# ElekShemaRelais.net
KiCad netlist of a schematic drawn in Altium Designer
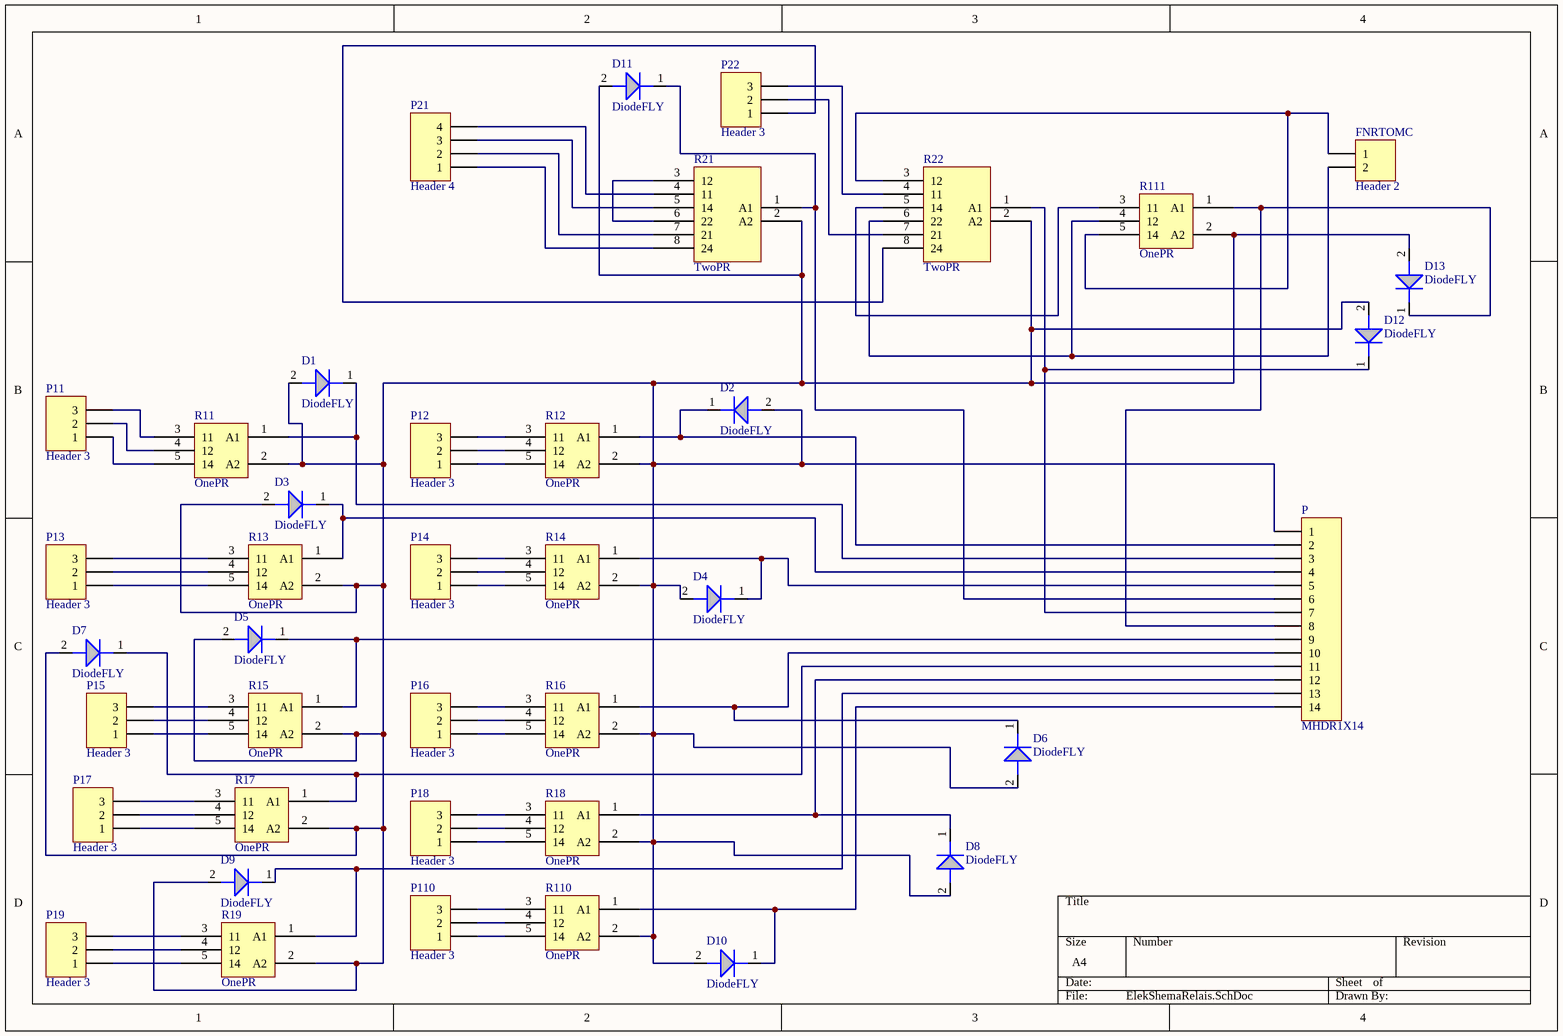
[diagram p0: ElekShemaRelais.SchDoc]

(export (version "E")
  (design (tool "Eeschema 10.0.6"))
  (components
    (comp (ref "D1") (value "DiodeFLY") (footprint "DiodeFLY") (libsource (lib "Schlib1") (part "DiodeFLY")))
    (comp (ref "D2") (value "DiodeFLY") (footprint "DiodeFLY") (libsource (lib "Schlib1") (part "DiodeFLY")))
    (comp (ref "D3") (value "DiodeFLY") (footprint "DiodeFLY") (libsource (lib "Schlib1") (part "DiodeFLY")))
    (comp (ref "D4") (value "DiodeFLY") (footprint "DiodeFLY") (libsource (lib "Schlib1") (part "DiodeFLY")))
    (comp (ref "D5") (value "DiodeFLY") (footprint "DiodeFLY") (libsource (lib "Schlib1") (part "DiodeFLY")))
    (comp (ref "D6") (value "DiodeFLY") (footprint "DiodeFLY") (libsource (lib "Schlib1") (part "DiodeFLY")))
    (comp (ref "D7") (value "DiodeFLY") (footprint "DiodeFLY") (libsource (lib "Schlib1") (part "DiodeFLY")))
    (comp (ref "D8") (value "DiodeFLY") (footprint "DiodeFLY") (libsource (lib "Schlib1") (part "DiodeFLY")))
    (comp (ref "D9") (value "DiodeFLY") (footprint "DiodeFLY") (libsource (lib "Schlib1") (part "DiodeFLY")))
    (comp (ref "D10") (value "DiodeFLY") (footprint "DiodeFLY") (libsource (lib "Schlib1") (part "DiodeFLY")))
    (comp (ref "D11") (value "DiodeFLY") (footprint "DiodeFLY") (libsource (lib "Schlib1") (part "DiodeFLY")))
    (comp (ref "D12") (value "DiodeFLY") (footprint "DiodeFLY") (libsource (lib "Schlib1") (part "DiodeFLY")))
    (comp (ref "D13") (value "DiodeFLY") (footprint "DiodeFLY") (libsource (lib "Schlib1") (part "DiodeFLY")))
    (comp (ref "FNRTOMC")
      (value "Header 2")
      (footprint "HDR2")
      (description "Header, 2-Pin")
      (fields (field (name "PUBLISHER") "Altium Limited"))
      (libsource (lib "Miscellaneous Connectors") (part "Header 2"))
    )
    (comp (ref "P")
      (value "MHDR1X14")
      (footprint "HDR14")
      (description "Header, 14-Pin")
      (fields (field (name "PUBLISHER") "Altium Limited"))
      (libsource (lib "Miscellaneous Connectors") (part "MHDR1X14"))
    )
    (comp (ref "P11")
      (value "Header 3")
      (footprint "HDR3")
      (description "Header, 3-Pin")
      (fields (field (name "PUBLISHER") "Altium Limited"))
      (libsource (lib "Miscellaneous Connectors") (part "Header 3"))
    )
    (comp (ref "P12")
      (value "Header 3")
      (footprint "HDR3")
      (description "Header, 3-Pin")
      (fields (field (name "PUBLISHER") "Altium Limited"))
      (libsource (lib "Miscellaneous Connectors") (part "Header 3"))
    )
    (comp (ref "P13")
      (value "Header 3")
      (footprint "HDR3")
      (description "Header, 3-Pin")
      (fields (field (name "PUBLISHER") "Altium Limited"))
      (libsource (lib "Miscellaneous Connectors") (part "Header 3"))
    )
    (comp (ref "P14")
      (value "Header 3")
      (footprint "HDR3")
      (description "Header, 3-Pin")
      (fields (field (name "PUBLISHER") "Altium Limited"))
      (libsource (lib "Miscellaneous Connectors") (part "Header 3"))
    )
    (comp (ref "P15")
      (value "Header 3")
      (footprint "HDR3")
      (description "Header, 3-Pin")
      (fields (field (name "PUBLISHER") "Altium Limited"))
      (libsource (lib "Miscellaneous Connectors") (part "Header 3"))
    )
    (comp (ref "P16")
      (value "Header 3")
      (footprint "HDR3")
      (description "Header, 3-Pin")
      (fields (field (name "PUBLISHER") "Altium Limited"))
      (libsource (lib "Miscellaneous Connectors") (part "Header 3"))
    )
    (comp (ref "P17")
      (value "Header 3")
      (footprint "HDR3")
      (description "Header, 3-Pin")
      (fields (field (name "PUBLISHER") "Altium Limited"))
      (libsource (lib "Miscellaneous Connectors") (part "Header 3"))
    )
    (comp (ref "P18")
      (value "Header 3")
      (footprint "HDR3")
      (description "Header, 3-Pin")
      (fields (field (name "PUBLISHER") "Altium Limited"))
      (libsource (lib "Miscellaneous Connectors") (part "Header 3"))
    )
    (comp (ref "P19")
      (value "Header 3")
      (footprint "HDR3")
      (description "Header, 3-Pin")
      (fields (field (name "PUBLISHER") "Altium Limited"))
      (libsource (lib "Miscellaneous Connectors") (part "Header 3"))
    )
    (comp (ref "P21")
      (value "Header 4")
      (footprint "HDR4")
      (description "Header, 4-Pin")
      (fields (field (name "PUBLISHER") "Altium Limited"))
      (libsource (lib "Miscellaneous Connectors") (part "Header 4"))
    )
    (comp (ref "P22")
      (value "Header 3")
      (footprint "HDR3")
      (description "Header, 3-Pin")
      (fields (field (name "PUBLISHER") "Altium Limited"))
      (libsource (lib "Miscellaneous Connectors") (part "Header 3"))
    )
    (comp (ref "P110")
      (value "Header 3")
      (footprint "HDR3")
      (description "Header, 3-Pin")
      (fields (field (name "PUBLISHER") "Altium Limited"))
      (libsource (lib "Miscellaneous Connectors") (part "Header 3"))
    )
    (comp (ref "R11") (value "OnePR") (footprint "EENPOOL") (libsource (lib "Schlib1") (part "R1")))
    (comp (ref "R12") (value "OnePR") (footprint "EENPOOL") (libsource (lib "Schlib1") (part "R1")))
    (comp (ref "R13") (value "OnePR") (footprint "EENPOOL") (libsource (lib "Schlib1") (part "R1")))
    (comp (ref "R14") (value "OnePR") (footprint "EENPOOL") (libsource (lib "Schlib1") (part "R1")))
    (comp (ref "R15") (value "OnePR") (footprint "EENPOOL") (libsource (lib "Schlib1") (part "R1")))
    (comp (ref "R16") (value "OnePR") (footprint "EENPOOL") (libsource (lib "Schlib1") (part "R1")))
    (comp (ref "R17") (value "OnePR") (footprint "EENPOOL") (libsource (lib "Schlib1") (part "R1")))
    (comp (ref "R18") (value "OnePR") (footprint "EENPOOL") (libsource (lib "Schlib1") (part "R1")))
    (comp (ref "R19") (value "OnePR") (footprint "EENPOOL") (libsource (lib "Schlib1") (part "R1")))
    (comp (ref "R21") (value "TwoPR") (footprint "TWEEPOOL") (libsource (lib "Schlib1") (part "R2")))
    (comp (ref "R22") (value "TwoPR") (footprint "TWEEPOOL") (libsource (lib "Schlib1") (part "R2")))
    (comp (ref "R110") (value "OnePR") (footprint "EENPOOL") (libsource (lib "Schlib1") (part "R1")))
    (comp (ref "R111") (value "OnePR") (footprint "EENPOOL") (libsource (lib "Schlib1") (part "R1")))
  )
  (nets
    (net (code "1") (name "Net-(R11-11)") (class "Default")
      (node (ref "P11") (pin "3") (pinfunction "3_3") (pintype "passive"))
      (node (ref "R11") (pin "3") (pinfunction "11_3") (pintype "passive"))
    )
    (net (code "2") (name "Net-(R11-12)") (class "Default")
      (node (ref "P11") (pin "2") (pinfunction "2_2") (pintype "passive"))
      (node (ref "R11") (pin "4") (pinfunction "12_4") (pintype "passive"))
    )
    (net (code "3") (name "Net-(R11-14)") (class "Default")
      (node (ref "P11") (pin "1") (pinfunction "1_1") (pintype "passive"))
      (node (ref "R11") (pin "5") (pinfunction "14_5") (pintype "passive"))
    )
    (net (code "4") (name "Net-(R11-A1)") (class "Default")
      (node (ref "D1") (pin "1") (pintype "passive"))
      (node (ref "P") (pin "3") (pinfunction "3_3") (pintype "passive"))
      (node (ref "R11") (pin "1") (pinfunction "A1_1") (pintype "passive"))
    )
    (net (code "5") (name "Net-(R11-A2)") (class "Default")
      (node (ref "D1") (pin "2") (pintype "passive"))
      (node (ref "D10") (pin "2") (pintype "passive"))
      (node (ref "D11") (pin "2") (pintype "passive"))
      (node (ref "D12") (pin "2") (pintype "passive"))
      (node (ref "D13") (pin "2") (pintype "passive"))
      (node (ref "D2") (pin "2") (pintype "passive"))
      (node (ref "D3") (pin "2") (pintype "passive"))
      (node (ref "D4") (pin "2") (pintype "passive"))
      (node (ref "D5") (pin "2") (pintype "passive"))
      (node (ref "D6") (pin "2") (pintype "passive"))
      (node (ref "D7") (pin "2") (pintype "passive"))
      (node (ref "D8") (pin "2") (pintype "passive"))
      (node (ref "D9") (pin "2") (pintype "passive"))
      (node (ref "P") (pin "1") (pinfunction "1_1") (pintype "passive"))
      (node (ref "R11") (pin "2") (pinfunction "A2_2") (pintype "passive"))
      (node (ref "R110") (pin "2") (pinfunction "A2_2") (pintype "passive"))
      (node (ref "R111") (pin "2") (pinfunction "A2_2") (pintype "passive"))
      (node (ref "R12") (pin "2") (pinfunction "A2_2") (pintype "passive"))
      (node (ref "R13") (pin "2") (pinfunction "A2_2") (pintype "passive"))
      (node (ref "R14") (pin "2") (pinfunction "A2_2") (pintype "passive"))
      (node (ref "R15") (pin "2") (pinfunction "A2_2") (pintype "passive"))
      (node (ref "R16") (pin "2") (pinfunction "A2_2") (pintype "passive"))
      (node (ref "R17") (pin "2") (pinfunction "A2_2") (pintype "passive"))
      (node (ref "R18") (pin "2") (pinfunction "A2_2") (pintype "passive"))
      (node (ref "R19") (pin "2") (pinfunction "A2_2") (pintype "passive"))
      (node (ref "R21") (pin "2") (pinfunction "A2_2") (pintype "passive"))
      (node (ref "R22") (pin "2") (pinfunction "A2_2") (pintype "passive"))
    )
    (net (code "6") (name "Net-(R12-11)") (class "Default")
      (node (ref "P12") (pin "3") (pinfunction "3_3") (pintype "passive"))
      (node (ref "R12") (pin "3") (pinfunction "11_3") (pintype "passive"))
    )
    (net (code "7") (name "Net-(R12-12)") (class "Default")
      (node (ref "P12") (pin "2") (pinfunction "2_2") (pintype "passive"))
      (node (ref "R12") (pin "4") (pinfunction "12_4") (pintype "passive"))
    )
    (net (code "8") (name "Net-(R12-14)") (class "Default")
      (node (ref "P12") (pin "1") (pinfunction "1_1") (pintype "passive"))
      (node (ref "R12") (pin "5") (pinfunction "14_5") (pintype "passive"))
    )
    (net (code "9") (name "Net-(R12-A1)") (class "Default")
      (node (ref "D2") (pin "1") (pintype "passive"))
      (node (ref "P") (pin "2") (pinfunction "2_2") (pintype "passive"))
      (node (ref "R12") (pin "1") (pinfunction "A1_1") (pintype "passive"))
    )
    (net (code "10") (name "Net-(R13-11)") (class "Default")
      (node (ref "P13") (pin "3") (pinfunction "3_3") (pintype "passive"))
      (node (ref "R13") (pin "3") (pinfunction "11_3") (pintype "passive"))
    )
    (net (code "11") (name "Net-(R13-12)") (class "Default")
      (node (ref "P13") (pin "2") (pinfunction "2_2") (pintype "passive"))
      (node (ref "R13") (pin "4") (pinfunction "12_4") (pintype "passive"))
    )
    (net (code "12") (name "Net-(R13-14)") (class "Default")
      (node (ref "P13") (pin "1") (pinfunction "1_1") (pintype "passive"))
      (node (ref "R13") (pin "5") (pinfunction "14_5") (pintype "passive"))
    )
    (net (code "13") (name "Net-(R13-A1)") (class "Default")
      (node (ref "D3") (pin "1") (pintype "passive"))
      (node (ref "P") (pin "4") (pinfunction "4_4") (pintype "passive"))
      (node (ref "R13") (pin "1") (pinfunction "A1_1") (pintype "passive"))
    )
    (net (code "14") (name "Net-(R14-11)") (class "Default")
      (node (ref "P14") (pin "3") (pinfunction "3_3") (pintype "passive"))
      (node (ref "R14") (pin "3") (pinfunction "11_3") (pintype "passive"))
    )
    (net (code "15") (name "Net-(R14-12)") (class "Default")
      (node (ref "P14") (pin "2") (pinfunction "2_2") (pintype "passive"))
      (node (ref "R14") (pin "4") (pinfunction "12_4") (pintype "passive"))
    )
    (net (code "16") (name "Net-(R14-14)") (class "Default")
      (node (ref "P14") (pin "1") (pinfunction "1_1") (pintype "passive"))
      (node (ref "R14") (pin "5") (pinfunction "14_5") (pintype "passive"))
    )
    (net (code "17") (name "Net-(R14-A1)") (class "Default")
      (node (ref "D4") (pin "1") (pintype "passive"))
      (node (ref "P") (pin "5") (pinfunction "5_5") (pintype "passive"))
      (node (ref "R14") (pin "1") (pinfunction "A1_1") (pintype "passive"))
    )
    (net (code "18") (name "Net-(R15-11)") (class "Default")
      (node (ref "P15") (pin "3") (pinfunction "3_3") (pintype "passive"))
      (node (ref "R15") (pin "3") (pinfunction "11_3") (pintype "passive"))
    )
    (net (code "19") (name "Net-(R15-12)") (class "Default")
      (node (ref "P15") (pin "2") (pinfunction "2_2") (pintype "passive"))
      (node (ref "R15") (pin "4") (pinfunction "12_4") (pintype "passive"))
    )
    (net (code "20") (name "Net-(R15-14)") (class "Default")
      (node (ref "P15") (pin "1") (pinfunction "1_1") (pintype "passive"))
      (node (ref "R15") (pin "5") (pinfunction "14_5") (pintype "passive"))
    )
    (net (code "21") (name "Net-(R15-A1)") (class "Default")
      (node (ref "D5") (pin "1") (pintype "passive"))
      (node (ref "P") (pin "9") (pinfunction "9_9") (pintype "passive"))
      (node (ref "R15") (pin "1") (pinfunction "A1_1") (pintype "passive"))
    )
    (net (code "22") (name "Net-(R16-11)") (class "Default")
      (node (ref "P16") (pin "3") (pinfunction "3_3") (pintype "passive"))
      (node (ref "R16") (pin "3") (pinfunction "11_3") (pintype "passive"))
    )
    (net (code "23") (name "Net-(R16-12)") (class "Default")
      (node (ref "P16") (pin "2") (pinfunction "2_2") (pintype "passive"))
      (node (ref "R16") (pin "4") (pinfunction "12_4") (pintype "passive"))
    )
    (net (code "24") (name "Net-(R16-14)") (class "Default")
      (node (ref "P16") (pin "1") (pinfunction "1_1") (pintype "passive"))
      (node (ref "R16") (pin "5") (pinfunction "14_5") (pintype "passive"))
    )
    (net (code "25") (name "Net-(R16-A1)") (class "Default")
      (node (ref "D6") (pin "1") (pintype "passive"))
      (node (ref "P") (pin "10") (pinfunction "10_10") (pintype "passive"))
      (node (ref "R16") (pin "1") (pinfunction "A1_1") (pintype "passive"))
    )
    (net (code "26") (name "Net-(R17-11)") (class "Default")
      (node (ref "P17") (pin "3") (pinfunction "3_3") (pintype "passive"))
      (node (ref "R17") (pin "3") (pinfunction "11_3") (pintype "passive"))
    )
    (net (code "27") (name "Net-(R17-12)") (class "Default")
      (node (ref "P17") (pin "2") (pinfunction "2_2") (pintype "passive"))
      (node (ref "R17") (pin "4") (pinfunction "12_4") (pintype "passive"))
    )
    (net (code "28") (name "Net-(R17-14)") (class "Default")
      (node (ref "P17") (pin "1") (pinfunction "1_1") (pintype "passive"))
      (node (ref "R17") (pin "5") (pinfunction "14_5") (pintype "passive"))
    )
    (net (code "29") (name "Net-(R17-A1)") (class "Default")
      (node (ref "D7") (pin "1") (pintype "passive"))
      (node (ref "P") (pin "11") (pinfunction "11_11") (pintype "passive"))
      (node (ref "R17") (pin "1") (pinfunction "A1_1") (pintype "passive"))
    )
    (net (code "30") (name "Net-(R18-11)") (class "Default")
      (node (ref "P18") (pin "3") (pinfunction "3_3") (pintype "passive"))
      (node (ref "R18") (pin "3") (pinfunction "11_3") (pintype "passive"))
    )
    (net (code "31") (name "Net-(R18-12)") (class "Default")
      (node (ref "P18") (pin "2") (pinfunction "2_2") (pintype "passive"))
      (node (ref "R18") (pin "4") (pinfunction "12_4") (pintype "passive"))
    )
    (net (code "32") (name "Net-(R18-14)") (class "Default")
      (node (ref "P18") (pin "1") (pinfunction "1_1") (pintype "passive"))
      (node (ref "R18") (pin "5") (pinfunction "14_5") (pintype "passive"))
    )
    (net (code "33") (name "Net-(R18-A1)") (class "Default")
      (node (ref "D8") (pin "1") (pintype "passive"))
      (node (ref "P") (pin "12") (pinfunction "12_12") (pintype "passive"))
      (node (ref "R18") (pin "1") (pinfunction "A1_1") (pintype "passive"))
    )
    (net (code "34") (name "Net-(R19-11)") (class "Default")
      (node (ref "P19") (pin "3") (pinfunction "3_3") (pintype "passive"))
      (node (ref "R19") (pin "3") (pinfunction "11_3") (pintype "passive"))
    )
    (net (code "35") (name "Net-(R19-12)") (class "Default")
      (node (ref "P19") (pin "2") (pinfunction "2_2") (pintype "passive"))
      (node (ref "R19") (pin "4") (pinfunction "12_4") (pintype "passive"))
    )
    (net (code "36") (name "Net-(R19-14)") (class "Default")
      (node (ref "P19") (pin "1") (pinfunction "1_1") (pintype "passive"))
      (node (ref "R19") (pin "5") (pinfunction "14_5") (pintype "passive"))
    )
    (net (code "37") (name "Net-(R19-A1)") (class "Default")
      (node (ref "D9") (pin "1") (pintype "passive"))
      (node (ref "P") (pin "13") (pinfunction "13_13") (pintype "passive"))
      (node (ref "R19") (pin "1") (pinfunction "A1_1") (pintype "passive"))
    )
    (net (code "38") (name "Net-(R21-11)") (class "Default")
      (node (ref "P21") (pin "4") (pinfunction "4_4") (pintype "passive"))
      (node (ref "R21") (pin "4") (pinfunction "11_4") (pintype "passive"))
    )
    (net (code "39") (name "Net-(R21-12)") (class "Default")
      (node (ref "R21") (pin "3") (pinfunction "12_3") (pintype "passive"))
      (node (ref "R21") (pin "6") (pinfunction "22_6") (pintype "passive"))
    )
    (net (code "40") (name "Net-(R21-14)") (class "Default")
      (node (ref "P21") (pin "3") (pinfunction "3_3") (pintype "passive"))
      (node (ref "R21") (pin "5") (pinfunction "14_5") (pintype "passive"))
    )
    (net (code "41") (name "Net-(R21-21)") (class "Default")
      (node (ref "P21") (pin "2") (pinfunction "2_2") (pintype "passive"))
      (node (ref "R21") (pin "7") (pinfunction "21_7") (pintype "passive"))
    )
    (net (code "42") (name "Net-(R21-24)") (class "Default")
      (node (ref "P21") (pin "1") (pinfunction "1_1") (pintype "passive"))
      (node (ref "R21") (pin "8") (pinfunction "24_8") (pintype "passive"))
    )
    (net (code "43") (name "Net-(R21-A1)") (class "Default")
      (node (ref "D11") (pin "1") (pintype "passive"))
      (node (ref "P") (pin "6") (pinfunction "6_6") (pintype "passive"))
      (node (ref "R21") (pin "1") (pinfunction "A1_1") (pintype "passive"))
    )
    (net (code "44") (name "Net-(R22-11)") (class "Default")
      (node (ref "P22") (pin "3") (pinfunction "3_3") (pintype "passive"))
      (node (ref "R22") (pin "4") (pinfunction "11_4") (pintype "passive"))
    )
    (net (code "45") (name "Net-(R22-21)") (class "Default")
      (node (ref "P22") (pin "2") (pinfunction "2_2") (pintype "passive"))
      (node (ref "R22") (pin "7") (pinfunction "21_7") (pintype "passive"))
    )
    (net (code "46") (name "Net-(R22-24)") (class "Default")
      (node (ref "P22") (pin "1") (pinfunction "1_1") (pintype "passive"))
      (node (ref "R22") (pin "8") (pinfunction "24_8") (pintype "passive"))
    )
    (net (code "47") (name "Net-(R22-A1)") (class "Default")
      (node (ref "D12") (pin "1") (pintype "passive"))
      (node (ref "P") (pin "7") (pinfunction "7_7") (pintype "passive"))
      (node (ref "R22") (pin "1") (pinfunction "A1_1") (pintype "passive"))
    )
    (net (code "48") (name "Net-(R110-11)") (class "Default")
      (node (ref "P110") (pin "3") (pinfunction "3_3") (pintype "passive"))
      (node (ref "R110") (pin "3") (pinfunction "11_3") (pintype "passive"))
    )
    (net (code "49") (name "Net-(R110-12)") (class "Default")
      (node (ref "P110") (pin "2") (pinfunction "2_2") (pintype "passive"))
      (node (ref "R110") (pin "4") (pinfunction "12_4") (pintype "passive"))
    )
    (net (code "50") (name "Net-(R110-14)") (class "Default")
      (node (ref "P110") (pin "1") (pinfunction "1_1") (pintype "passive"))
      (node (ref "R110") (pin "5") (pinfunction "14_5") (pintype "passive"))
    )
    (net (code "51") (name "Net-(R110-A1)") (class "Default")
      (node (ref "D10") (pin "1") (pintype "passive"))
      (node (ref "P") (pin "14") (pinfunction "14_14") (pintype "passive"))
      (node (ref "R110") (pin "1") (pinfunction "A1_1") (pintype "passive"))
    )
    (net (code "52") (name "Net-(R111-11)") (class "Default")
      (node (ref "R111") (pin "3") (pinfunction "11_3") (pintype "passive"))
      (node (ref "R22") (pin "5") (pinfunction "14_5") (pintype "passive"))
    )
    (net (code "53") (name "Net-(R111-12)") (class "Default")
      (node (ref "FNRTOMC") (pin "2") (pinfunction "2_2") (pintype "passive"))
      (node (ref "R111") (pin "4") (pinfunction "12_4") (pintype "passive"))
      (node (ref "R22") (pin "6") (pinfunction "22_6") (pintype "passive"))
    )
    (net (code "54") (name "Net-(R111-14)") (class "Default")
      (node (ref "FNRTOMC") (pin "1") (pinfunction "1_1") (pintype "passive"))
      (node (ref "R111") (pin "5") (pinfunction "14_5") (pintype "passive"))
      (node (ref "R22") (pin "3") (pinfunction "12_3") (pintype "passive"))
    )
    (net (code "55") (name "Net-(R111-A1)") (class "Default")
      (node (ref "D13") (pin "1") (pintype "passive"))
      (node (ref "P") (pin "8") (pinfunction "8_8") (pintype "passive"))
      (node (ref "R111") (pin "1") (pinfunction "A1_1") (pintype "passive"))
    )
  )
)
